# demo_dermis_main_testboard_inamps.net
KiCad netlist of a schematic drawn in Altium Designer
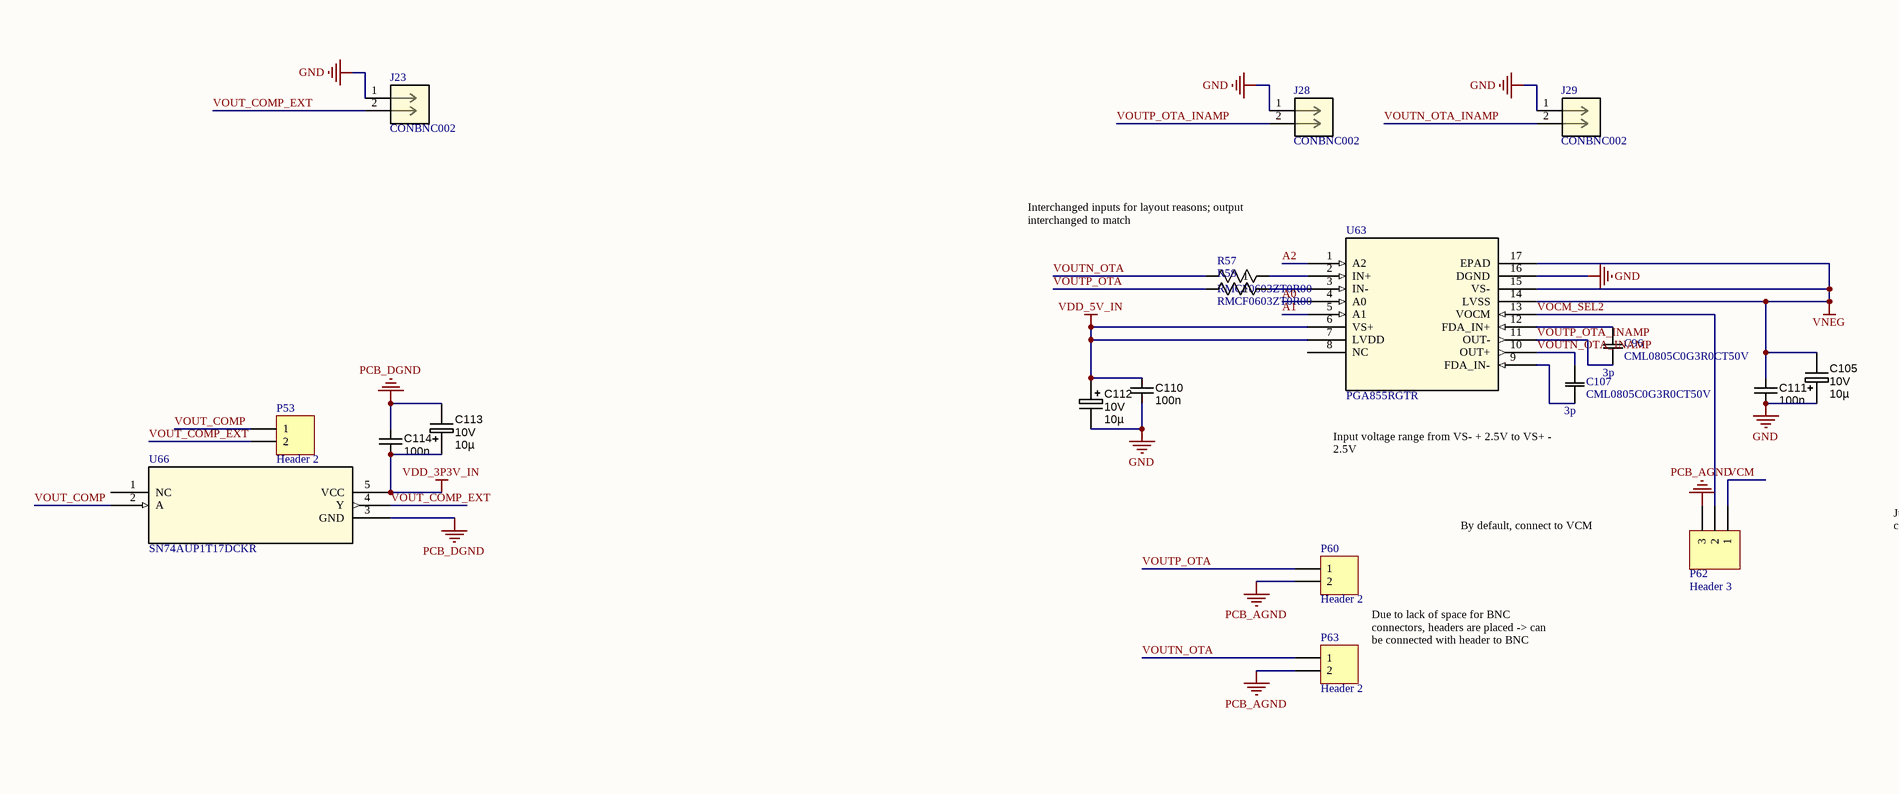
[diagram p0: demo_dermis_main_testboard_inamps.SchDoc, left]
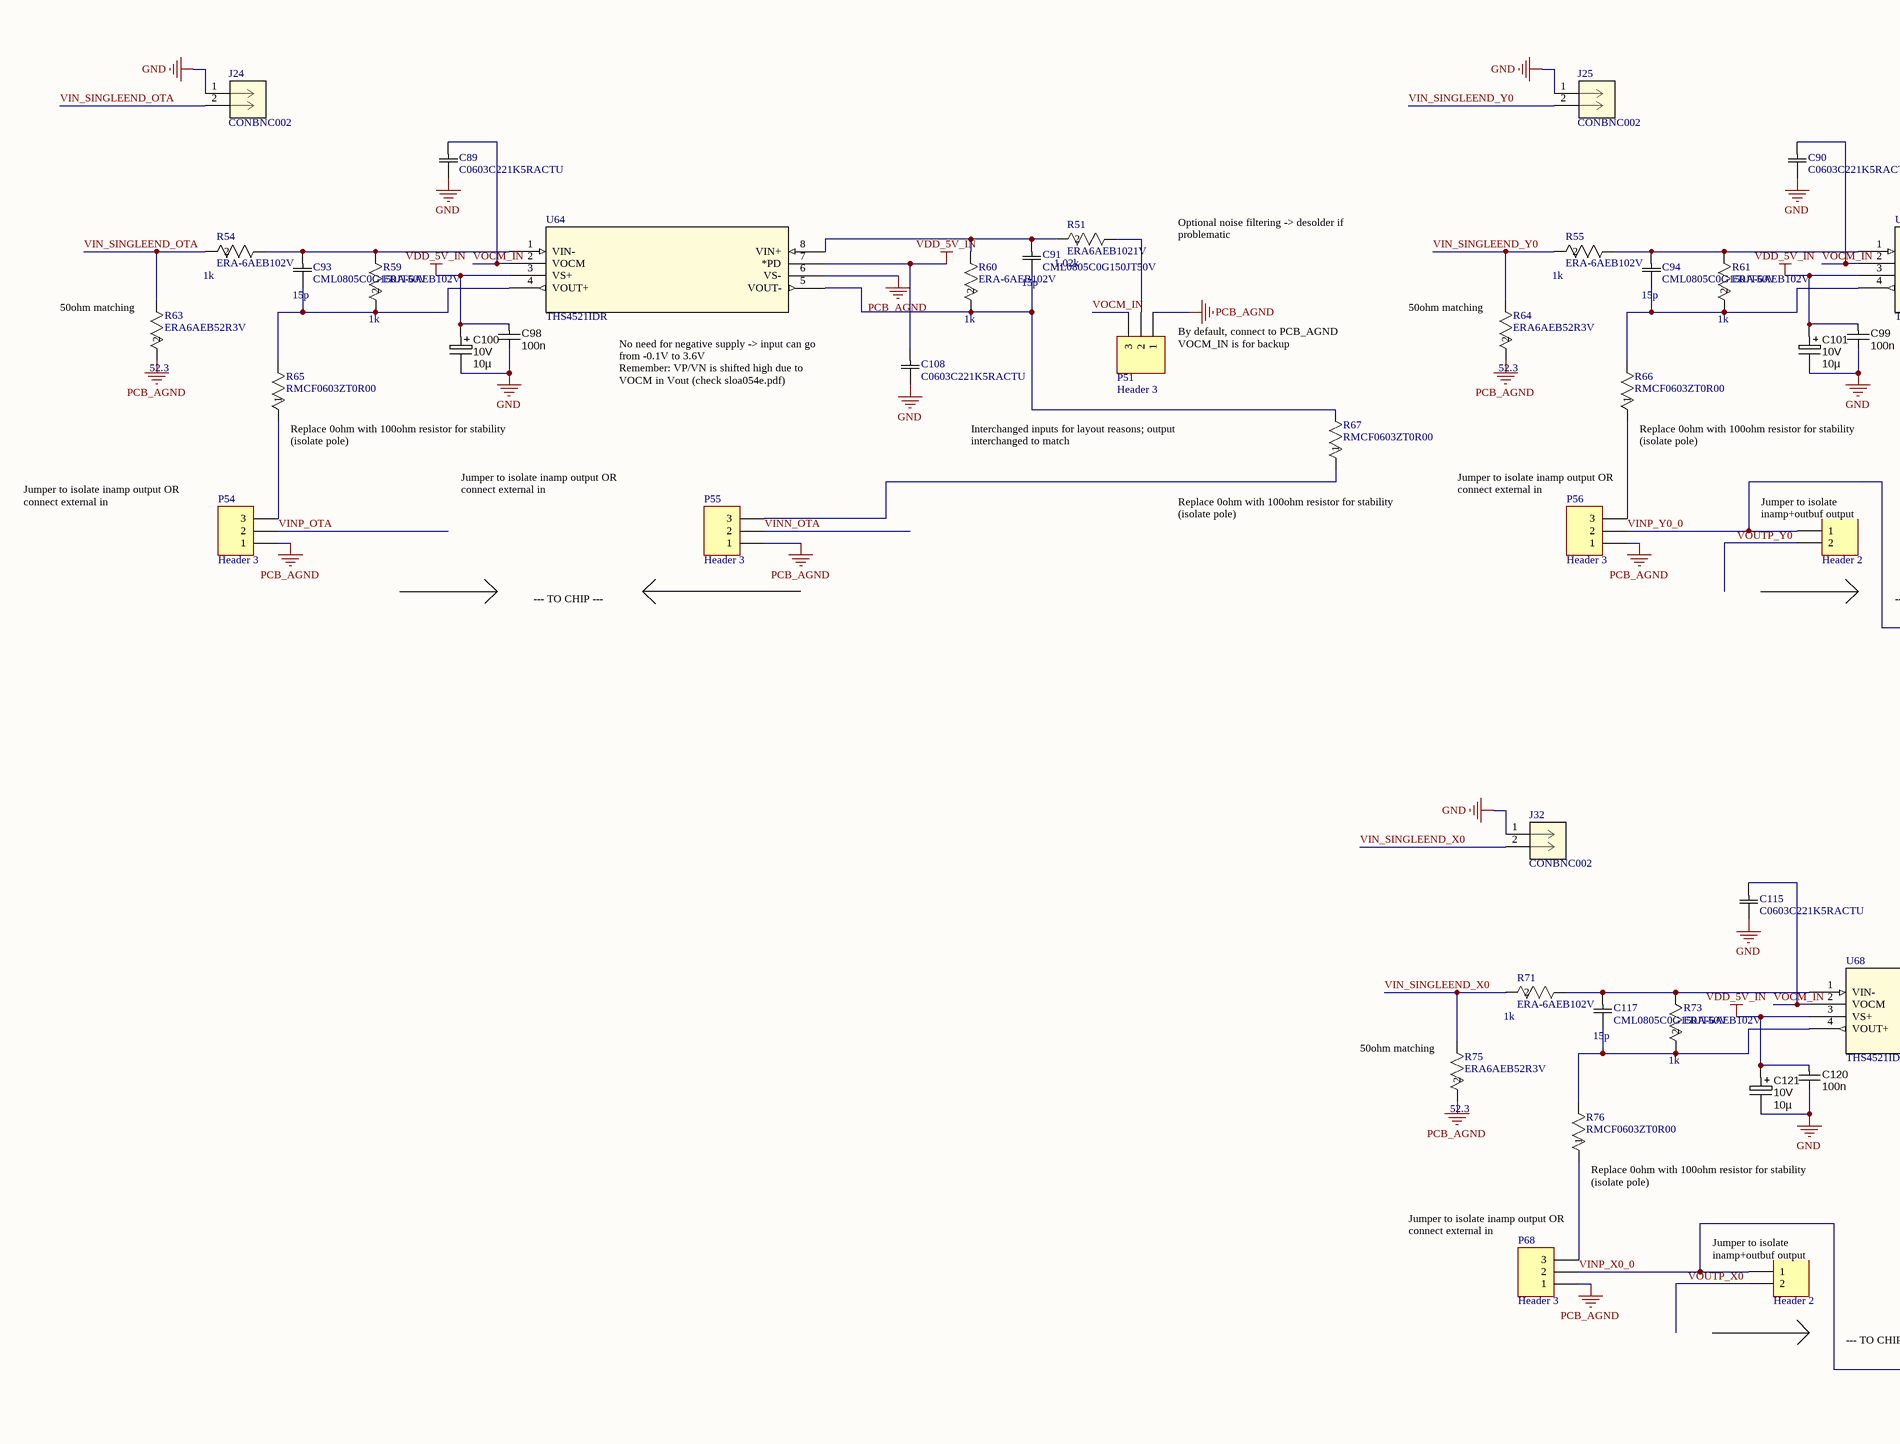
[diagram p1: demo_dermis_main_testboard_inamps.SchDoc, middle]
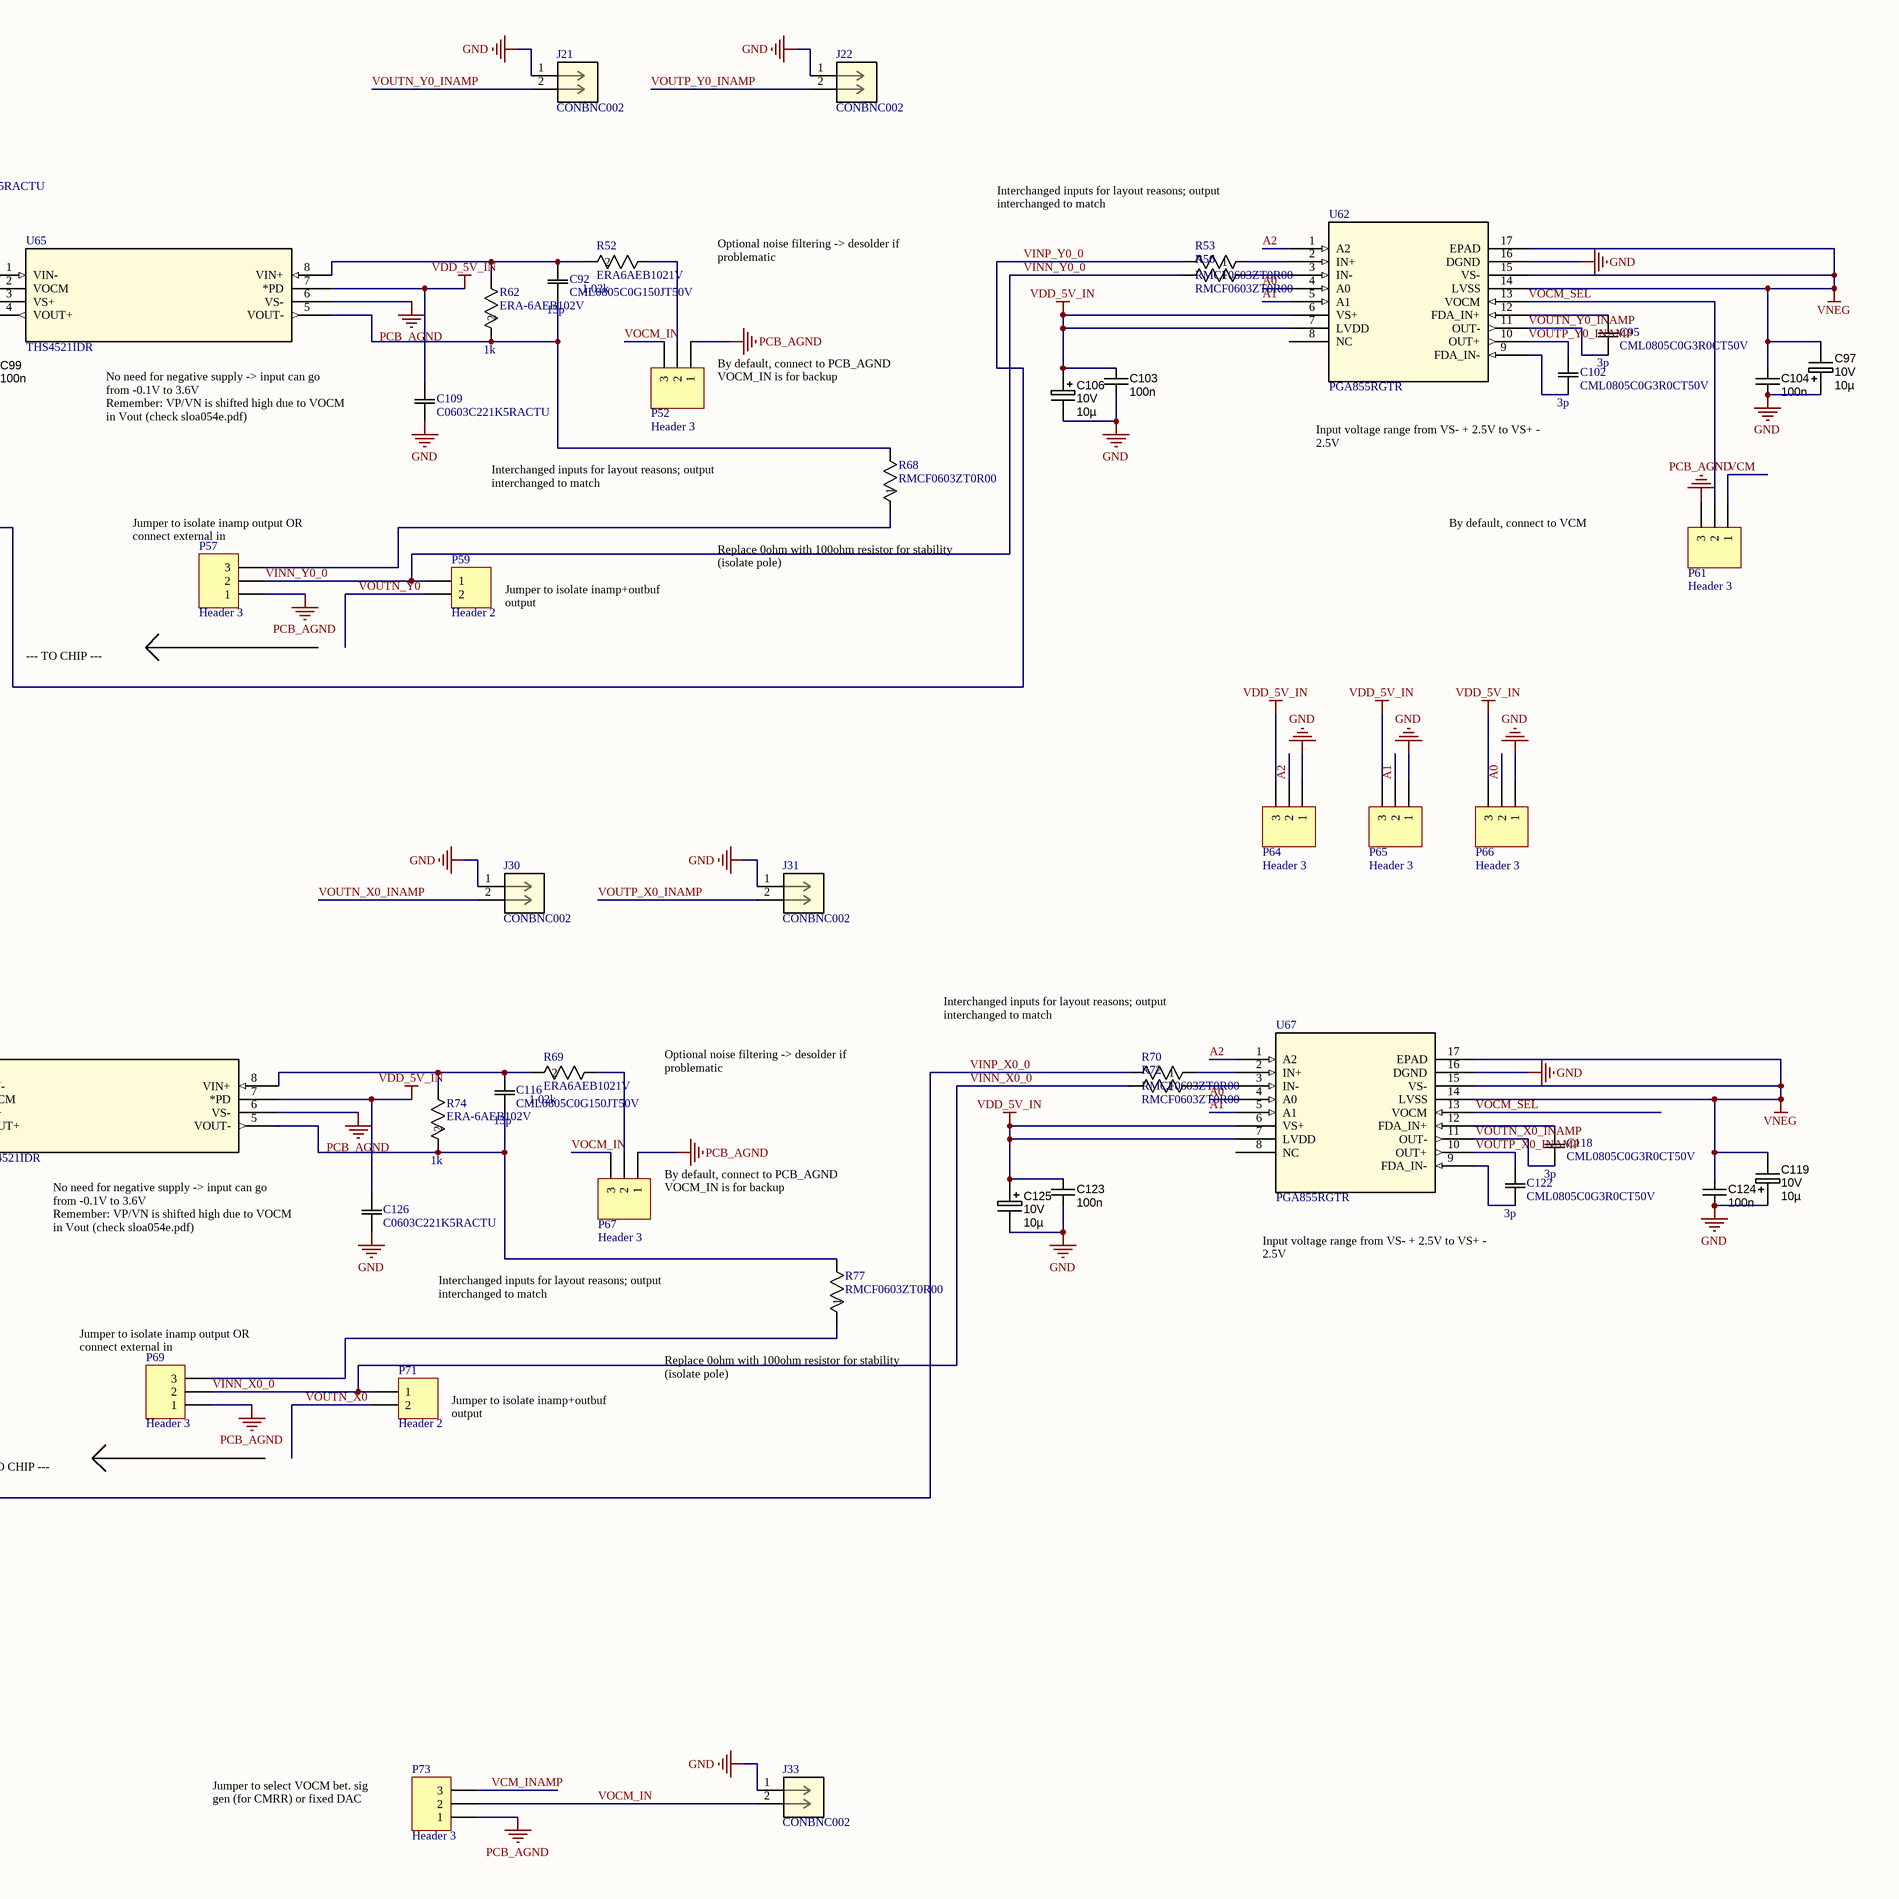
[diagram p2: demo_dermis_main_testboard_inamps.SchDoc, right]

(export (version "E")
  (design (tool "Eeschema 10.0.6"))
  (components
    (comp (ref "C89")
      (value "C0603C221K5RACTU")
      (footprint "CAPC17595_87N_KEM")
      (description "No Description Available")
      (libsource (lib "C0603C221K5RACTU") (part "C0603C221K5RACTU"))
    )
    (comp (ref "C90")
      (value "C0603C221K5RACTU")
      (footprint "CAPC17595_87N_KEM")
      (description "No Description Available")
      (libsource (lib "C0603C221K5RACTU") (part "C0603C221K5RACTU"))
    )
    (comp (ref "C91")
      (value "CML0805C0G150JT50V")
      (footprint "CAP_CML_0805_.3pF-1500pF,4700pF_STP")
      (description "No Description Available")
      (fields (field (name "ALTIUM_VALUE") "15p"))
      (libsource (lib "CML0805C0G150JT50V") (part "CML0805C0G150JT50V"))
    )
    (comp (ref "C92")
      (value "CML0805C0G150JT50V")
      (footprint "CAP_CML_0805_.3pF-1500pF,4700pF_STP")
      (description "No Description Available")
      (fields (field (name "ALTIUM_VALUE") "15p"))
      (libsource (lib "CML0805C0G150JT50V") (part "CML0805C0G150JT50V"))
    )
    (comp (ref "C93")
      (value "CML0805C0G150JT50V")
      (footprint "CAP_CML_0805_.3pF-1500pF,4700pF_STP")
      (description "No Description Available")
      (fields (field (name "ALTIUM_VALUE") "15p"))
      (libsource (lib "CML0805C0G150JT50V") (part "CML0805C0G150JT50V"))
    )
    (comp (ref "C94")
      (value "CML0805C0G150JT50V")
      (footprint "CAP_CML_0805_.3pF-1500pF,4700pF_STP")
      (description "No Description Available")
      (fields (field (name "ALTIUM_VALUE") "15p"))
      (libsource (lib "CML0805C0G150JT50V") (part "CML0805C0G150JT50V"))
    )
    (comp (ref "C95")
      (value "CML0805C0G3R0CT50V")
      (footprint "CAP_CML_0805_.3pF-1500pF,4700pF_STP")
      (description "No Description Available")
      (fields (field (name "ALTIUM_VALUE") "3p"))
      (libsource (lib "CML0805C0G3R0CT50V") (part "CML0805C0G3R0CT50V"))
    )
    (comp (ref "C96")
      (value "CML0805C0G3R0CT50V")
      (footprint "CAP_CML_0805_.3pF-1500pF,4700pF_STP")
      (description "No Description Available")
      (fields (field (name "ALTIUM_VALUE") "3p"))
      (libsource (lib "CML0805C0G3R0CT50V") (part "CML0805C0G3R0CT50V"))
    )
    (comp (ref "C97")
      (value "10µ")
      (footprint "CAPMP2012X150USR")
      (description "Capacitor SMD Tantalum 10uF 20% 10V 0805")
      (fields (field (name "TOLERANCE") "±20%") (field (name "RATINGS") "10V"))
      (libsource (lib "PBL - Capacitors") (part "CAPT_10u_0805_10V"))
    )
    (comp (ref "C98")
      (value "100n")
      (footprint "CAPC1608N")
      (description "Capacitor SMD Cer 100nF 10% 50V X7R 0603")
      (fields (field (name "TOLERANCE") "±10%") (field (name "Comment") "approved sub OK"))
      (libsource (lib "PBL - Capacitors") (part "CAPC_100n_0603"))
    )
    (comp (ref "C99")
      (value "100n")
      (footprint "CAPC1608N")
      (description "Capacitor SMD Cer 100nF 10% 50V X7R 0603")
      (fields (field (name "TOLERANCE") "±10%") (field (name "Comment") "approved sub OK"))
      (libsource (lib "PBL - Capacitors") (part "CAPC_100n_0603"))
    )
    (comp (ref "C100")
      (value "10µ")
      (footprint "CAPMP2012X150USR")
      (description "Capacitor SMD Tantalum 10uF 20% 10V 0805")
      (fields (field (name "TOLERANCE") "±20%") (field (name "RATINGS") "10V"))
      (libsource (lib "PBL - Capacitors") (part "CAPT_10u_0805_10V"))
    )
    (comp (ref "C101")
      (value "10µ")
      (footprint "CAPMP2012X150USR")
      (description "Capacitor SMD Tantalum 10uF 20% 10V 0805")
      (fields (field (name "TOLERANCE") "±20%") (field (name "RATINGS") "10V"))
      (libsource (lib "PBL - Capacitors") (part "CAPT_10u_0805_10V"))
    )
    (comp (ref "C102")
      (value "CML0805C0G3R0CT50V")
      (footprint "CAP_CML_0805_.3pF-1500pF,4700pF_STP")
      (description "No Description Available")
      (fields (field (name "ALTIUM_VALUE") "3p"))
      (libsource (lib "CML0805C0G3R0CT50V") (part "CML0805C0G3R0CT50V"))
    )
    (comp (ref "C103")
      (value "100n")
      (footprint "CAPC1608N")
      (description "Capacitor SMD Cer 100nF 10% 50V X7R 0603")
      (fields (field (name "TOLERANCE") "±10%") (field (name "Comment") "approved sub OK"))
      (libsource (lib "PBL - Capacitors") (part "CAPC_100n_0603"))
    )
    (comp (ref "C104")
      (value "100n")
      (footprint "CAPC1608N")
      (description "Capacitor SMD Cer 100nF 10% 50V X7R 0603")
      (fields (field (name "TOLERANCE") "±10%") (field (name "Comment") "approved sub OK"))
      (libsource (lib "PBL - Capacitors") (part "CAPC_100n_0603"))
    )
    (comp (ref "C105")
      (value "10µ")
      (footprint "CAPMP2012X150USR")
      (description "Capacitor SMD Tantalum 10uF 20% 10V 0805")
      (fields (field (name "TOLERANCE") "±20%") (field (name "RATINGS") "10V"))
      (libsource (lib "PBL - Capacitors") (part "CAPT_10u_0805_10V"))
    )
    (comp (ref "C106")
      (value "10µ")
      (footprint "CAPMP2012X150USR")
      (description "Capacitor SMD Tantalum 10uF 20% 10V 0805")
      (fields (field (name "TOLERANCE") "±20%") (field (name "RATINGS") "10V"))
      (libsource (lib "PBL - Capacitors") (part "CAPT_10u_0805_10V"))
    )
    (comp (ref "C107")
      (value "CML0805C0G3R0CT50V")
      (footprint "CAP_CML_0805_.3pF-1500pF,4700pF_STP")
      (description "No Description Available")
      (fields (field (name "ALTIUM_VALUE") "3p"))
      (libsource (lib "CML0805C0G3R0CT50V") (part "CML0805C0G3R0CT50V"))
    )
    (comp (ref "C108")
      (value "C0603C221K5RACTU")
      (footprint "CAPC17595_87N_KEM")
      (description "No Description Available")
      (libsource (lib "C0603C221K5RACTU") (part "C0603C221K5RACTU"))
    )
    (comp (ref "C109")
      (value "C0603C221K5RACTU")
      (footprint "CAPC17595_87N_KEM")
      (description "No Description Available")
      (libsource (lib "C0603C221K5RACTU") (part "C0603C221K5RACTU"))
    )
    (comp (ref "C110")
      (value "100n")
      (footprint "CAPC1608N")
      (description "Capacitor SMD Cer 100nF 10% 50V X7R 0603")
      (fields (field (name "TOLERANCE") "±10%") (field (name "Comment") "approved sub OK"))
      (libsource (lib "PBL - Capacitors") (part "CAPC_100n_0603"))
    )
    (comp (ref "C111")
      (value "100n")
      (footprint "CAPC1608N")
      (description "Capacitor SMD Cer 100nF 10% 50V X7R 0603")
      (fields (field (name "TOLERANCE") "±10%") (field (name "Comment") "approved sub OK"))
      (libsource (lib "PBL - Capacitors") (part "CAPC_100n_0603"))
    )
    (comp (ref "C112")
      (value "10µ")
      (footprint "CAPMP2012X150USR")
      (description "Capacitor SMD Tantalum 10uF 20% 10V 0805")
      (fields (field (name "TOLERANCE") "±20%") (field (name "RATINGS") "10V"))
      (libsource (lib "PBL - Capacitors") (part "CAPT_10u_0805_10V"))
    )
    (comp (ref "C113")
      (value "10µ")
      (footprint "CAPMP2012X150USR")
      (description "Capacitor SMD Tantalum 10uF 20% 10V 0805")
      (fields (field (name "TOLERANCE") "±20%") (field (name "RATINGS") "10V"))
      (libsource (lib "PBL - Capacitors") (part "CAPT_10u_0805_10V"))
    )
    (comp (ref "C114")
      (value "100n")
      (footprint "CAPC1608N")
      (description "Capacitor SMD Cer 100nF 10% 50V X7R 0603")
      (fields (field (name "TOLERANCE") "±10%") (field (name "Comment") "approved sub OK"))
      (libsource (lib "PBL - Capacitors") (part "CAPC_100n_0603"))
    )
    (comp (ref "C115")
      (value "C0603C221K5RACTU")
      (footprint "CAPC17595_87N_KEM")
      (description "No Description Available")
      (libsource (lib "C0603C221K5RACTU") (part "C0603C221K5RACTU"))
    )
    (comp (ref "C116")
      (value "CML0805C0G150JT50V")
      (footprint "CAP_CML_0805_.3pF-1500pF,4700pF_STP")
      (description "No Description Available")
      (fields (field (name "ALTIUM_VALUE") "15p"))
      (libsource (lib "CML0805C0G150JT50V") (part "CML0805C0G150JT50V"))
    )
    (comp (ref "C117")
      (value "CML0805C0G150JT50V")
      (footprint "CAP_CML_0805_.3pF-1500pF,4700pF_STP")
      (description "No Description Available")
      (fields (field (name "ALTIUM_VALUE") "15p"))
      (libsource (lib "CML0805C0G150JT50V") (part "CML0805C0G150JT50V"))
    )
    (comp (ref "C118")
      (value "CML0805C0G3R0CT50V")
      (footprint "CAP_CML_0805_.3pF-1500pF,4700pF_STP")
      (description "No Description Available")
      (fields (field (name "ALTIUM_VALUE") "3p"))
      (libsource (lib "CML0805C0G3R0CT50V") (part "CML0805C0G3R0CT50V"))
    )
    (comp (ref "C119")
      (value "10µ")
      (footprint "CAPMP2012X150USR")
      (description "Capacitor SMD Tantalum 10uF 20% 10V 0805")
      (fields (field (name "TOLERANCE") "±20%") (field (name "RATINGS") "10V"))
      (libsource (lib "PBL - Capacitors") (part "CAPT_10u_0805_10V"))
    )
    (comp (ref "C120")
      (value "100n")
      (footprint "CAPC1608N")
      (description "Capacitor SMD Cer 100nF 10% 50V X7R 0603")
      (fields (field (name "TOLERANCE") "±10%") (field (name "Comment") "approved sub OK"))
      (libsource (lib "PBL - Capacitors") (part "CAPC_100n_0603"))
    )
    (comp (ref "C121")
      (value "10µ")
      (footprint "CAPMP2012X150USR")
      (description "Capacitor SMD Tantalum 10uF 20% 10V 0805")
      (fields (field (name "TOLERANCE") "±20%") (field (name "RATINGS") "10V"))
      (libsource (lib "PBL - Capacitors") (part "CAPT_10u_0805_10V"))
    )
    (comp (ref "C122")
      (value "CML0805C0G3R0CT50V")
      (footprint "CAP_CML_0805_.3pF-1500pF,4700pF_STP")
      (description "No Description Available")
      (fields (field (name "ALTIUM_VALUE") "3p"))
      (libsource (lib "CML0805C0G3R0CT50V") (part "CML0805C0G3R0CT50V"))
    )
    (comp (ref "C123")
      (value "100n")
      (footprint "CAPC1608N")
      (description "Capacitor SMD Cer 100nF 10% 50V X7R 0603")
      (fields (field (name "TOLERANCE") "±10%") (field (name "Comment") "approved sub OK"))
      (libsource (lib "PBL - Capacitors") (part "CAPC_100n_0603"))
    )
    (comp (ref "C124")
      (value "100n")
      (footprint "CAPC1608N")
      (description "Capacitor SMD Cer 100nF 10% 50V X7R 0603")
      (fields (field (name "TOLERANCE") "±10%") (field (name "Comment") "approved sub OK"))
      (libsource (lib "PBL - Capacitors") (part "CAPC_100n_0603"))
    )
    (comp (ref "C125")
      (value "10µ")
      (footprint "CAPMP2012X150USR")
      (description "Capacitor SMD Tantalum 10uF 20% 10V 0805")
      (fields (field (name "TOLERANCE") "±20%") (field (name "RATINGS") "10V"))
      (libsource (lib "PBL - Capacitors") (part "CAPT_10u_0805_10V"))
    )
    (comp (ref "C126")
      (value "C0603C221K5RACTU")
      (footprint "CAPC17595_87N_KEM")
      (description "No Description Available")
      (libsource (lib "C0603C221K5RACTU") (part "C0603C221K5RACTU"))
    )
    (comp (ref "J21")
      (value "CONBNC002")
      (footprint "CONN_CONBN_LNX")
      (description "No Description Available")
      (libsource (lib "CONBNC002") (part "CONBNC002"))
    )
    (comp (ref "J22")
      (value "CONBNC002")
      (footprint "CONN_CONBN_LNX")
      (description "No Description Available")
      (libsource (lib "CONBNC002") (part "CONBNC002"))
    )
    (comp (ref "J23")
      (value "CONBNC002")
      (footprint "CONN_CONBN_LNX")
      (description "No Description Available")
      (libsource (lib "CONBNC002") (part "CONBNC002"))
    )
    (comp (ref "J24")
      (value "CONBNC002")
      (footprint "CONN_CONBN_LNX")
      (description "No Description Available")
      (libsource (lib "CONBNC002") (part "CONBNC002"))
    )
    (comp (ref "J25")
      (value "CONBNC002")
      (footprint "CONN_CONBN_LNX")
      (description "No Description Available")
      (libsource (lib "CONBNC002") (part "CONBNC002"))
    )
    (comp (ref "J28")
      (value "CONBNC002")
      (footprint "CONN_CONBN_LNX")
      (description "No Description Available")
      (libsource (lib "CONBNC002") (part "CONBNC002"))
    )
    (comp (ref "J29")
      (value "CONBNC002")
      (footprint "CONN_CONBN_LNX")
      (description "No Description Available")
      (libsource (lib "CONBNC002") (part "CONBNC002"))
    )
    (comp (ref "J30")
      (value "CONBNC002")
      (footprint "CONN_CONBN_LNX")
      (description "No Description Available")
      (libsource (lib "CONBNC002") (part "CONBNC002"))
    )
    (comp (ref "J31")
      (value "CONBNC002")
      (footprint "CONN_CONBN_LNX")
      (description "No Description Available")
      (libsource (lib "CONBNC002") (part "CONBNC002"))
    )
    (comp (ref "J32")
      (value "CONBNC002")
      (footprint "CONN_CONBN_LNX")
      (description "No Description Available")
      (libsource (lib "CONBNC002") (part "CONBNC002"))
    )
    (comp (ref "J33")
      (value "CONBNC002")
      (footprint "CONN_CONBN_LNX")
      (description "No Description Available")
      (libsource (lib "CONBNC002") (part "CONBNC002"))
    )
    (comp (ref "P51")
      (value "Header 3")
      (footprint "HDR1X3")
      (description "Header, 3-Pin")
      (fields (field (name "PUBLISHER") "Altium Limited"))
      (libsource (lib "") (part "Header 3_1"))
    )
    (comp (ref "P52")
      (value "Header 3")
      (footprint "HDR1X3")
      (description "Header, 3-Pin")
      (fields (field (name "PUBLISHER") "Altium Limited"))
      (libsource (lib "") (part "Header 3_1"))
    )
    (comp (ref "P53")
      (value "Header 2")
      (footprint "HDR1X2")
      (description "Header, 2-Pin")
      (fields (field (name "PUBLISHER") "Altium Limited"))
      (libsource (lib "Miscellaneous Connectors") (part "Header 2"))
    )
    (comp (ref "P54")
      (value "Header 3")
      (footprint "HDR1X3")
      (description "Header, 3-Pin")
      (fields (field (name "PUBLISHER") "Altium Limited"))
      (libsource (lib "Miscellaneous Connectors") (part "Header 3"))
    )
    (comp (ref "P55")
      (value "Header 3")
      (footprint "HDR1X3")
      (description "Header, 3-Pin")
      (fields (field (name "PUBLISHER") "Altium Limited"))
      (libsource (lib "Miscellaneous Connectors") (part "Header 3"))
    )
    (comp (ref "P56")
      (value "Header 3")
      (footprint "HDR1X3")
      (description "Header, 3-Pin")
      (fields (field (name "PUBLISHER") "Altium Limited"))
      (libsource (lib "Miscellaneous Connectors") (part "Header 3"))
    )
    (comp (ref "P57")
      (value "Header 3")
      (footprint "HDR1X3")
      (description "Header, 3-Pin")
      (fields (field (name "PUBLISHER") "Altium Limited"))
      (libsource (lib "Miscellaneous Connectors") (part "Header 3"))
    )
    (comp (ref "P58")
      (value "Header 2")
      (footprint "HDR1X2")
      (description "Header, 2-Pin")
      (fields (field (name "PUBLISHER") "Altium Limited"))
      (libsource (lib "Miscellaneous Connectors") (part "Header 2"))
    )
    (comp (ref "P59")
      (value "Header 2")
      (footprint "HDR1X2")
      (description "Header, 2-Pin")
      (fields (field (name "PUBLISHER") "Altium Limited"))
      (libsource (lib "Miscellaneous Connectors") (part "Header 2"))
    )
    (comp (ref "P60")
      (value "Header 2")
      (footprint "HDR1X2")
      (description "Header, 2-Pin")
      (fields (field (name "PUBLISHER") "Altium Limited"))
      (libsource (lib "Miscellaneous Connectors") (part "Header 2"))
    )
    (comp (ref "P61")
      (value "Header 3")
      (footprint "HDR1X3")
      (description "Header, 3-Pin")
      (fields (field (name "PUBLISHER") "Altium Limited"))
      (libsource (lib "") (part "Header 3_1"))
    )
    (comp (ref "P62")
      (value "Header 3")
      (footprint "HDR1X3")
      (description "Header, 3-Pin")
      (fields (field (name "PUBLISHER") "Altium Limited"))
      (libsource (lib "") (part "Header 3_1"))
    )
    (comp (ref "P63")
      (value "Header 2")
      (footprint "HDR1X2")
      (description "Header, 2-Pin")
      (fields (field (name "PUBLISHER") "Altium Limited"))
      (libsource (lib "Miscellaneous Connectors") (part "Header 2"))
    )
    (comp (ref "P64")
      (value "Header 3")
      (footprint "HDR1X3")
      (description "Header, 3-Pin")
      (fields (field (name "PUBLISHER") "Altium Limited"))
      (libsource (lib "") (part "Header 3_1"))
    )
    (comp (ref "P65")
      (value "Header 3")
      (footprint "HDR1X3")
      (description "Header, 3-Pin")
      (fields (field (name "PUBLISHER") "Altium Limited"))
      (libsource (lib "") (part "Header 3_1"))
    )
    (comp (ref "P66")
      (value "Header 3")
      (footprint "HDR1X3")
      (description "Header, 3-Pin")
      (fields (field (name "PUBLISHER") "Altium Limited"))
      (libsource (lib "") (part "Header 3_1"))
    )
    (comp (ref "P67")
      (value "Header 3")
      (footprint "HDR1X3")
      (description "Header, 3-Pin")
      (fields (field (name "PUBLISHER") "Altium Limited"))
      (libsource (lib "") (part "Header 3_1"))
    )
    (comp (ref "P68")
      (value "Header 3")
      (footprint "HDR1X3")
      (description "Header, 3-Pin")
      (fields (field (name "PUBLISHER") "Altium Limited"))
      (libsource (lib "Miscellaneous Connectors") (part "Header 3"))
    )
    (comp (ref "P69")
      (value "Header 3")
      (footprint "HDR1X3")
      (description "Header, 3-Pin")
      (fields (field (name "PUBLISHER") "Altium Limited"))
      (libsource (lib "Miscellaneous Connectors") (part "Header 3"))
    )
    (comp (ref "P70")
      (value "Header 2")
      (footprint "HDR1X2")
      (description "Header, 2-Pin")
      (fields (field (name "PUBLISHER") "Altium Limited"))
      (libsource (lib "Miscellaneous Connectors") (part "Header 2"))
    )
    (comp (ref "P71")
      (value "Header 2")
      (footprint "HDR1X2")
      (description "Header, 2-Pin")
      (fields (field (name "PUBLISHER") "Altium Limited"))
      (libsource (lib "Miscellaneous Connectors") (part "Header 2"))
    )
    (comp (ref "P73")
      (value "Header 3")
      (footprint "HDR1X3")
      (description "Header, 3-Pin")
      (fields (field (name "PUBLISHER") "Altium Limited"))
      (libsource (lib "Miscellaneous Connectors") (part "Header 3"))
    )
    (comp (ref "R51")
      (value "ERA6AEB1021V")
      (footprint "RES_ERA6A_0805_PAN")
      (description "No Description Available")
      (fields (field (name "ALTIUM_VALUE") "1.02k"))
      (libsource (lib "ERA6AEB1021V") (part "ERA6AEB1021V"))
    )
    (comp (ref "R52")
      (value "ERA6AEB1021V")
      (footprint "RES_ERA6A_0805_PAN")
      (description "No Description Available")
      (fields (field (name "ALTIUM_VALUE") "1.02k"))
      (libsource (lib "ERA6AEB1021V") (part "ERA6AEB1021V"))
    )
    (comp (ref "R53")
      (value "RMCF0603ZT0R00")
      (footprint "STA_RMCF0603_STP")
      (description "No Description Available")
      (libsource (lib "RMCF0603ZT0R00") (part "RMCF0603ZT0R00"))
    )
    (comp (ref "R54")
      (value "ERA-6AEB102V")
      (footprint "RC0805N_PAN")
      (description "No Description Available")
      (fields (field (name "ALTIUM_VALUE") "1k"))
      (libsource (lib "ERA-6AEB102V") (part "ERA-6AEB102V"))
    )
    (comp (ref "R55")
      (value "ERA-6AEB102V")
      (footprint "RC0805N_PAN")
      (description "No Description Available")
      (fields (field (name "ALTIUM_VALUE") "1k"))
      (libsource (lib "ERA-6AEB102V") (part "ERA-6AEB102V"))
    )
    (comp (ref "R56")
      (value "RMCF0603ZT0R00")
      (footprint "STA_RMCF0603_STP")
      (description "No Description Available")
      (libsource (lib "RMCF0603ZT0R00") (part "RMCF0603ZT0R00"))
    )
    (comp (ref "R57")
      (value "RMCF0603ZT0R00")
      (footprint "STA_RMCF0603_STP")
      (description "No Description Available")
      (libsource (lib "RMCF0603ZT0R00") (part "RMCF0603ZT0R00"))
    )
    (comp (ref "R58")
      (value "RMCF0603ZT0R00")
      (footprint "STA_RMCF0603_STP")
      (description "No Description Available")
      (libsource (lib "RMCF0603ZT0R00") (part "RMCF0603ZT0R00"))
    )
    (comp (ref "R59")
      (value "ERA-6AEB102V")
      (footprint "RC0805N_PAN")
      (description "No Description Available")
      (fields (field (name "ALTIUM_VALUE") "1k"))
      (libsource (lib "ERA-6AEB102V") (part "ERA-6AEB102V"))
    )
    (comp (ref "R60")
      (value "ERA-6AEB102V")
      (footprint "RC0805N_PAN")
      (description "No Description Available")
      (fields (field (name "ALTIUM_VALUE") "1k"))
      (libsource (lib "ERA-6AEB102V") (part "ERA-6AEB102V"))
    )
    (comp (ref "R61")
      (value "ERA-6AEB102V")
      (footprint "RC0805N_PAN")
      (description "No Description Available")
      (fields (field (name "ALTIUM_VALUE") "1k"))
      (libsource (lib "ERA-6AEB102V") (part "ERA-6AEB102V"))
    )
    (comp (ref "R62")
      (value "ERA-6AEB102V")
      (footprint "RC0805N_PAN")
      (description "No Description Available")
      (fields (field (name "ALTIUM_VALUE") "1k"))
      (libsource (lib "ERA-6AEB102V") (part "ERA-6AEB102V"))
    )
    (comp (ref "R63")
      (value "ERA6AEB52R3V")
      (footprint "RES_ERA6A_0805_PAN")
      (description "No Description Available")
      (fields (field (name "ALTIUM_VALUE") "52.3"))
      (libsource (lib "ERA6AEB52R3V") (part "ERA6AEB52R3V"))
    )
    (comp (ref "R64")
      (value "ERA6AEB52R3V")
      (footprint "RES_ERA6A_0805_PAN")
      (description "No Description Available")
      (fields (field (name "ALTIUM_VALUE") "52.3"))
      (libsource (lib "ERA6AEB52R3V") (part "ERA6AEB52R3V"))
    )
    (comp (ref "R65")
      (value "RMCF0603ZT0R00")
      (footprint "STA_RMCF0603_STP")
      (description "No Description Available")
      (libsource (lib "RMCF0603ZT0R00") (part "RMCF0603ZT0R00"))
    )
    (comp (ref "R66")
      (value "RMCF0603ZT0R00")
      (footprint "STA_RMCF0603_STP")
      (description "No Description Available")
      (libsource (lib "RMCF0603ZT0R00") (part "RMCF0603ZT0R00"))
    )
    (comp (ref "R67")
      (value "RMCF0603ZT0R00")
      (footprint "STA_RMCF0603_STP")
      (description "No Description Available")
      (libsource (lib "RMCF0603ZT0R00") (part "RMCF0603ZT0R00"))
    )
    (comp (ref "R68")
      (value "RMCF0603ZT0R00")
      (footprint "STA_RMCF0603_STP")
      (description "No Description Available")
      (libsource (lib "RMCF0603ZT0R00") (part "RMCF0603ZT0R00"))
    )
    (comp (ref "R69")
      (value "ERA6AEB1021V")
      (footprint "RES_ERA6A_0805_PAN")
      (description "No Description Available")
      (fields (field (name "ALTIUM_VALUE") "1.02k"))
      (libsource (lib "ERA6AEB1021V") (part "ERA6AEB1021V"))
    )
    (comp (ref "R70")
      (value "RMCF0603ZT0R00")
      (footprint "STA_RMCF0603_STP")
      (description "No Description Available")
      (libsource (lib "RMCF0603ZT0R00") (part "RMCF0603ZT0R00"))
    )
    (comp (ref "R71")
      (value "ERA-6AEB102V")
      (footprint "RC0805N_PAN")
      (description "No Description Available")
      (fields (field (name "ALTIUM_VALUE") "1k"))
      (libsource (lib "ERA-6AEB102V") (part "ERA-6AEB102V"))
    )
    (comp (ref "R72")
      (value "RMCF0603ZT0R00")
      (footprint "STA_RMCF0603_STP")
      (description "No Description Available")
      (libsource (lib "RMCF0603ZT0R00") (part "RMCF0603ZT0R00"))
    )
    (comp (ref "R73")
      (value "ERA-6AEB102V")
      (footprint "RC0805N_PAN")
      (description "No Description Available")
      (fields (field (name "ALTIUM_VALUE") "1k"))
      (libsource (lib "ERA-6AEB102V") (part "ERA-6AEB102V"))
    )
    (comp (ref "R74")
      (value "ERA-6AEB102V")
      (footprint "RC0805N_PAN")
      (description "No Description Available")
      (fields (field (name "ALTIUM_VALUE") "1k"))
      (libsource (lib "ERA-6AEB102V") (part "ERA-6AEB102V"))
    )
    (comp (ref "R75")
      (value "ERA6AEB52R3V")
      (footprint "RES_ERA6A_0805_PAN")
      (description "No Description Available")
      (fields (field (name "ALTIUM_VALUE") "52.3"))
      (libsource (lib "ERA6AEB52R3V") (part "ERA6AEB52R3V"))
    )
    (comp (ref "R76")
      (value "RMCF0603ZT0R00")
      (footprint "STA_RMCF0603_STP")
      (description "No Description Available")
      (libsource (lib "RMCF0603ZT0R00") (part "RMCF0603ZT0R00"))
    )
    (comp (ref "R77")
      (value "RMCF0603ZT0R00")
      (footprint "STA_RMCF0603_STP")
      (description "No Description Available")
      (libsource (lib "RMCF0603ZT0R00") (part "RMCF0603ZT0R00"))
    )
    (comp (ref "U62")
      (value "PGA855RGTR")
      (footprint "VQFN16_RGT_TEX")
      (description "No Description Available")
      (libsource (lib "PGA855RGTR") (part "PGA855RGTR"))
    )
    (comp (ref "U63")
      (value "PGA855RGTR")
      (footprint "VQFN16_RGT_TEX")
      (description "No Description Available")
      (libsource (lib "PGA855RGTR") (part "PGA855RGTR"))
    )
    (comp (ref "U64")
      (value "THS4521IDR")
      (footprint "D8")
      (description "No Description Available")
      (libsource (lib "THS4521IDR") (part "THS4521IDR"))
    )
    (comp (ref "U65")
      (value "THS4521IDR")
      (footprint "D8")
      (description "No Description Available")
      (libsource (lib "THS4521IDR") (part "THS4521IDR"))
    )
    (comp (ref "U66")
      (value "SN74AUP1T17DCKR")
      (footprint "DCK5")
      (description "No Description Available")
      (libsource (lib "SN74AUP1T17DCKR") (part "SN74AUP1T17DCKR"))
    )
    (comp (ref "U67")
      (value "PGA855RGTR")
      (footprint "VQFN16_RGT_TEX")
      (description "No Description Available")
      (libsource (lib "PGA855RGTR") (part "PGA855RGTR"))
    )
    (comp (ref "U68")
      (value "THS4521IDR")
      (footprint "D8")
      (description "No Description Available")
      (libsource (lib "THS4521IDR") (part "THS4521IDR"))
    )
  )
  (nets
    (net (code "1") (name "/A0") (class "Default")
      (node (ref "P66") (pin "2") (pinfunction "2_2") (pintype "passive"))
      (node (ref "U62") (pin "4") (pinfunction "A0_4") (pintype "input"))
      (node (ref "U63") (pin "4") (pinfunction "A0_4") (pintype "input"))
      (node (ref "U67") (pin "4") (pinfunction "A0_4") (pintype "input"))
    )
    (net (code "2") (name "/A1") (class "Default")
      (node (ref "P65") (pin "2") (pinfunction "2_2") (pintype "passive"))
      (node (ref "U62") (pin "5") (pinfunction "A1_5") (pintype "input"))
      (node (ref "U63") (pin "5") (pinfunction "A1_5") (pintype "input"))
      (node (ref "U67") (pin "5") (pinfunction "A1_5") (pintype "input"))
    )
    (net (code "3") (name "/A2") (class "Default")
      (node (ref "P64") (pin "2") (pinfunction "2_2") (pintype "passive"))
      (node (ref "U62") (pin "1") (pinfunction "A2_1") (pintype "input"))
      (node (ref "U63") (pin "1") (pinfunction "A2_1") (pintype "input"))
      (node (ref "U67") (pin "1") (pinfunction "A2_1") (pintype "input"))
    )
    (net (code "4") (name "/VCM") (class "Default")
      (node (ref "P61") (pin "1") (pinfunction "1_1") (pintype "passive"))
      (node (ref "P62") (pin "1") (pinfunction "1_1") (pintype "passive"))
    )
    (net (code "5") (name "/VCM_INAMP") (class "Default")
      (node (ref "P73") (pin "3") (pinfunction "3_3") (pintype "passive"))
    )
    (net (code "6") (name "/VINN_OTA") (class "Default")
      (node (ref "P55") (pin "2") (pinfunction "2_2") (pintype "passive"))
    )
    (net (code "7") (name "/VINN_X0_0") (class "Default")
      (node (ref "P69") (pin "2") (pinfunction "2_2") (pintype "passive"))
      (node (ref "P71") (pin "1") (pinfunction "1_1") (pintype "passive"))
      (node (ref "R72") (pin "2") (pinfunction "2_2") (pintype "passive"))
    )
    (net (code "8") (name "/VINN_Y0_0") (class "Default")
      (node (ref "P57") (pin "2") (pinfunction "2_2") (pintype "passive"))
      (node (ref "P59") (pin "1") (pinfunction "1_1") (pintype "passive"))
      (node (ref "R56") (pin "2") (pinfunction "2_2") (pintype "passive"))
    )
    (net (code "9") (name "/VINP_OTA") (class "Default")
      (node (ref "P54") (pin "2") (pinfunction "2_2") (pintype "passive"))
    )
    (net (code "10") (name "/VINP_X0_0") (class "Default")
      (node (ref "P68") (pin "2") (pinfunction "2_2") (pintype "passive"))
      (node (ref "P70") (pin "1") (pinfunction "1_1") (pintype "passive"))
      (node (ref "R70") (pin "2") (pinfunction "2_2") (pintype "passive"))
    )
    (net (code "11") (name "/VINP_Y0_0") (class "Default")
      (node (ref "P56") (pin "2") (pinfunction "2_2") (pintype "passive"))
      (node (ref "P58") (pin "1") (pinfunction "1_1") (pintype "passive"))
      (node (ref "R53") (pin "2") (pinfunction "2_2") (pintype "passive"))
    )
    (net (code "12") (name "/VIN_SINGLEEND_OTA") (class "Default")
      (node (ref "J24") (pin "2") (pinfunction "2_2") (pintype "passive"))
      (node (ref "R54") (pin "2") (pinfunction "2_2") (pintype "passive"))
      (node (ref "R63") (pin "1") (pinfunction "1_1") (pintype "passive"))
    )
    (net (code "13") (name "/VIN_SINGLEEND_X0") (class "Default")
      (node (ref "J32") (pin "2") (pinfunction "2_2") (pintype "passive"))
      (node (ref "R71") (pin "2") (pinfunction "2_2") (pintype "passive"))
      (node (ref "R75") (pin "1") (pinfunction "1_1") (pintype "passive"))
    )
    (net (code "14") (name "/VIN_SINGLEEND_Y0") (class "Default")
      (node (ref "J25") (pin "2") (pinfunction "2_2") (pintype "passive"))
      (node (ref "R55") (pin "2") (pinfunction "2_2") (pintype "passive"))
      (node (ref "R64") (pin "1") (pinfunction "1_1") (pintype "passive"))
    )
    (net (code "15") (name "/VOCM_IN") (class "Default")
      (node (ref "C115") (pin "1") (pinfunction "1_1") (pintype "passive"))
      (node (ref "C89") (pin "1") (pinfunction "1_1") (pintype "passive"))
      (node (ref "C90") (pin "1") (pinfunction "1_1") (pintype "passive"))
      (node (ref "J33") (pin "2") (pinfunction "2_2") (pintype "passive"))
      (node (ref "P51") (pin "3") (pinfunction "3_3") (pintype "passive"))
      (node (ref "P52") (pin "3") (pinfunction "3_3") (pintype "passive"))
      (node (ref "P67") (pin "3") (pinfunction "3_3") (pintype "passive"))
      (node (ref "P73") (pin "2") (pinfunction "2_2") (pintype "passive"))
      (node (ref "U64") (pin "2") (pinfunction "VOCM_2") (pintype "passive"))
      (node (ref "U65") (pin "2") (pinfunction "VOCM_2") (pintype "passive"))
      (node (ref "U68") (pin "2") (pinfunction "VOCM_2") (pintype "passive"))
    )
    (net (code "16") (name "/VOCM_SEL") (class "Default")
      (node (ref "P61") (pin "2") (pinfunction "2_2") (pintype "passive"))
      (node (ref "U62") (pin "13") (pinfunction "VOCM_13") (pintype "input"))
      (node (ref "U67") (pin "13") (pinfunction "VOCM_13") (pintype "input"))
    )
    (net (code "17") (name "/VOCM_SEL2") (class "Default")
      (node (ref "P62") (pin "2") (pinfunction "2_2") (pintype "passive"))
      (node (ref "U63") (pin "13") (pinfunction "VOCM_13") (pintype "input"))
    )
    (net (code "18") (name "/VOUTN_OTA") (class "Default")
      (node (ref "P63") (pin "1") (pinfunction "1_1") (pintype "passive"))
      (node (ref "R57") (pin "2") (pinfunction "2_2") (pintype "passive"))
    )
    (net (code "19") (name "/VOUTN_OTA_INAMP") (class "Default")
      (node (ref "C107") (pin "2") (pinfunction "2_2") (pintype "passive"))
      (node (ref "J29") (pin "2") (pinfunction "2_2") (pintype "passive"))
      (node (ref "U63") (pin "10") (pinfunction "OUT+_10") (pintype "output"))
    )
    (net (code "20") (name "/VOUTN_X0") (class "Default")
      (node (ref "P71") (pin "2") (pinfunction "2_2") (pintype "passive"))
    )
    (net (code "21") (name "/VOUTN_X0_INAMP") (class "Default")
      (node (ref "C118") (pin "1") (pinfunction "1_1") (pintype "passive"))
      (node (ref "J30") (pin "2") (pinfunction "2_2") (pintype "passive"))
      (node (ref "U67") (pin "11") (pinfunction "OUT-_11") (pintype "output"))
    )
    (net (code "22") (name "/VOUTN_Y0") (class "Default")
      (node (ref "P59") (pin "2") (pinfunction "2_2") (pintype "passive"))
    )
    (net (code "23") (name "/VOUTN_Y0_INAMP") (class "Default")
      (node (ref "C95") (pin "1") (pinfunction "1_1") (pintype "passive"))
      (node (ref "J21") (pin "2") (pinfunction "2_2") (pintype "passive"))
      (node (ref "U62") (pin "11") (pinfunction "OUT-_11") (pintype "output"))
    )
    (net (code "24") (name "/VOUTP_OTA") (class "Default")
      (node (ref "P60") (pin "1") (pinfunction "1_1") (pintype "passive"))
      (node (ref "R58") (pin "2") (pinfunction "2_2") (pintype "passive"))
    )
    (net (code "25") (name "/VOUTP_OTA_INAMP") (class "Default")
      (node (ref "C96") (pin "1") (pinfunction "1_1") (pintype "passive"))
      (node (ref "J28") (pin "2") (pinfunction "2_2") (pintype "passive"))
      (node (ref "U63") (pin "11") (pinfunction "OUT-_11") (pintype "output"))
    )
    (net (code "26") (name "/VOUTP_X0") (class "Default")
      (node (ref "P70") (pin "2") (pinfunction "2_2") (pintype "passive"))
    )
    (net (code "27") (name "/VOUTP_X0_INAMP") (class "Default")
      (node (ref "C122") (pin "2") (pinfunction "2_2") (pintype "passive"))
      (node (ref "J31") (pin "2") (pinfunction "2_2") (pintype "passive"))
      (node (ref "U67") (pin "10") (pinfunction "OUT+_10") (pintype "output"))
    )
    (net (code "28") (name "/VOUTP_Y0") (class "Default")
      (node (ref "P58") (pin "2") (pinfunction "2_2") (pintype "passive"))
    )
    (net (code "29") (name "/VOUTP_Y0_INAMP") (class "Default")
      (node (ref "C102") (pin "2") (pinfunction "2_2") (pintype "passive"))
      (node (ref "J22") (pin "2") (pinfunction "2_2") (pintype "passive"))
      (node (ref "U62") (pin "10") (pinfunction "OUT+_10") (pintype "output"))
    )
    (net (code "30") (name "/VOUT_COMP") (class "Default")
      (node (ref "P53") (pin "1") (pinfunction "1_1") (pintype "passive"))
      (node (ref "U66") (pin "2") (pinfunction "A_2") (pintype "input"))
    )
    (net (code "31") (name "/VOUT_COMP_EXT") (class "Default")
      (node (ref "J23") (pin "2") (pinfunction "2_2") (pintype "passive"))
      (node (ref "P53") (pin "2") (pinfunction "2_2") (pintype "passive"))
      (node (ref "U66") (pin "4") (pinfunction "Y_4") (pintype "output"))
    )
    (net (code "32") (name "GND") (class "Default")
      (node (ref "C100") (pin "2") (pintype "passive"))
      (node (ref "C101") (pin "2") (pintype "passive"))
      (node (ref "C103") (pin "2") (pintype "passive"))
      (node (ref "C104") (pin "1") (pintype "passive"))
      (node (ref "C105") (pin "1") (pintype "passive"))
      (node (ref "C106") (pin "2") (pintype "passive"))
      (node (ref "C108") (pin "2") (pinfunction "2_2") (pintype "passive"))
      (node (ref "C109") (pin "2") (pinfunction "2_2") (pintype "passive"))
      (node (ref "C110") (pin "2") (pintype "passive"))
      (node (ref "C111") (pin "1") (pintype "passive"))
      (node (ref "C112") (pin "2") (pintype "passive"))
      (node (ref "C115") (pin "2") (pinfunction "2_2") (pintype "passive"))
      (node (ref "C119") (pin "1") (pintype "passive"))
      (node (ref "C120") (pin "2") (pintype "passive"))
      (node (ref "C121") (pin "2") (pintype "passive"))
      (node (ref "C123") (pin "2") (pintype "passive"))
      (node (ref "C124") (pin "1") (pintype "passive"))
      (node (ref "C125") (pin "2") (pintype "passive"))
      (node (ref "C126") (pin "2") (pinfunction "2_2") (pintype "passive"))
      (node (ref "C89") (pin "2") (pinfunction "2_2") (pintype "passive"))
      (node (ref "C90") (pin "2") (pinfunction "2_2") (pintype "passive"))
      (node (ref "C97") (pin "1") (pintype "passive"))
      (node (ref "C98") (pin "2") (pintype "passive"))
      (node (ref "C99") (pin "2") (pintype "passive"))
      (node (ref "J21") (pin "1") (pinfunction "1_1") (pintype "passive"))
      (node (ref "J22") (pin "1") (pinfunction "1_1") (pintype "passive"))
      (node (ref "J23") (pin "1") (pinfunction "1_1") (pintype "passive"))
      (node (ref "J24") (pin "1") (pinfunction "1_1") (pintype "passive"))
      (node (ref "J25") (pin "1") (pinfunction "1_1") (pintype "passive"))
      (node (ref "J28") (pin "1") (pinfunction "1_1") (pintype "passive"))
      (node (ref "J29") (pin "1") (pinfunction "1_1") (pintype "passive"))
      (node (ref "J30") (pin "1") (pinfunction "1_1") (pintype "passive"))
      (node (ref "J31") (pin "1") (pinfunction "1_1") (pintype "passive"))
      (node (ref "J32") (pin "1") (pinfunction "1_1") (pintype "passive"))
      (node (ref "J33") (pin "1") (pinfunction "1_1") (pintype "passive"))
      (node (ref "P64") (pin "1") (pinfunction "1_1") (pintype "passive"))
      (node (ref "P65") (pin "1") (pinfunction "1_1") (pintype "passive"))
      (node (ref "P66") (pin "1") (pinfunction "1_1") (pintype "passive"))
      (node (ref "U62") (pin "16") (pinfunction "DGND_16") (pintype "power_in"))
      (node (ref "U63") (pin "16") (pinfunction "DGND_16") (pintype "power_in"))
      (node (ref "U67") (pin "16") (pinfunction "DGND_16") (pintype "power_in"))
    )
    (net (code "33") (name "Net-(P51-Pad2)") (class "Default")
      (node (ref "P51") (pin "2") (pinfunction "2_2") (pintype "passive"))
      (node (ref "R51") (pin "1") (pinfunction "1_1") (pintype "passive"))
    )
    (net (code "34") (name "Net-(P52-Pad2)") (class "Default")
      (node (ref "P52") (pin "2") (pinfunction "2_2") (pintype "passive"))
      (node (ref "R52") (pin "1") (pinfunction "1_1") (pintype "passive"))
    )
    (net (code "35") (name "Net-(P54-Pad3)") (class "Default")
      (node (ref "P54") (pin "3") (pinfunction "3_3") (pintype "passive"))
      (node (ref "R65") (pin "1") (pinfunction "1_1") (pintype "passive"))
    )
    (net (code "36") (name "Net-(P55-Pad3)") (class "Default")
      (node (ref "P55") (pin "3") (pinfunction "3_3") (pintype "passive"))
      (node (ref "R67") (pin "1") (pinfunction "1_1") (pintype "passive"))
    )
    (net (code "37") (name "Net-(P56-Pad3)") (class "Default")
      (node (ref "P56") (pin "3") (pinfunction "3_3") (pintype "passive"))
      (node (ref "R66") (pin "1") (pinfunction "1_1") (pintype "passive"))
    )
    (net (code "38") (name "Net-(P57-Pad3)") (class "Default")
      (node (ref "P57") (pin "3") (pinfunction "3_3") (pintype "passive"))
      (node (ref "R68") (pin "1") (pinfunction "1_1") (pintype "passive"))
    )
    (net (code "39") (name "Net-(P67-Pad2)") (class "Default")
      (node (ref "P67") (pin "2") (pinfunction "2_2") (pintype "passive"))
      (node (ref "R69") (pin "1") (pinfunction "1_1") (pintype "passive"))
    )
    (net (code "40") (name "Net-(P68-Pad3)") (class "Default")
      (node (ref "P68") (pin "3") (pinfunction "3_3") (pintype "passive"))
      (node (ref "R76") (pin "1") (pinfunction "1_1") (pintype "passive"))
    )
    (net (code "41") (name "Net-(P69-Pad3)") (class "Default")
      (node (ref "P69") (pin "3") (pinfunction "3_3") (pintype "passive"))
      (node (ref "R77") (pin "1") (pinfunction "1_1") (pintype "passive"))
    )
    (net (code "42") (name "Net-(U62-FDA_IN+)") (class "Default")
      (node (ref "C95") (pin "2") (pinfunction "2_2") (pintype "passive"))
      (node (ref "U62") (pin "12") (pinfunction "FDA_IN+_12") (pintype "input"))
    )
    (net (code "43") (name "Net-(U62-FDA_IN-)") (class "Default")
      (node (ref "C102") (pin "1") (pinfunction "1_1") (pintype "passive"))
      (node (ref "U62") (pin "9") (pinfunction "FDA_IN-_9") (pintype "input"))
    )
    (net (code "44") (name "Net-(U62-IN+)") (class "Default")
      (node (ref "R53") (pin "1") (pinfunction "1_1") (pintype "passive"))
      (node (ref "U62") (pin "2") (pinfunction "IN+_2") (pintype "input"))
    )
    (net (code "45") (name "Net-(U62-IN-)") (class "Default")
      (node (ref "R56") (pin "1") (pinfunction "1_1") (pintype "passive"))
      (node (ref "U62") (pin "3") (pinfunction "IN-_3") (pintype "input"))
    )
    (net (code "46") (name "Net-(U63-FDA_IN+)") (class "Default")
      (node (ref "C96") (pin "2") (pinfunction "2_2") (pintype "passive"))
      (node (ref "U63") (pin "12") (pinfunction "FDA_IN+_12") (pintype "input"))
    )
    (net (code "47") (name "Net-(U63-FDA_IN-)") (class "Default")
      (node (ref "C107") (pin "1") (pinfunction "1_1") (pintype "passive"))
      (node (ref "U63") (pin "9") (pinfunction "FDA_IN-_9") (pintype "input"))
    )
    (net (code "48") (name "Net-(U63-IN+)") (class "Default")
      (node (ref "R57") (pin "1") (pinfunction "1_1") (pintype "passive"))
      (node (ref "U63") (pin "2") (pinfunction "IN+_2") (pintype "input"))
    )
    (net (code "49") (name "Net-(U63-IN-)") (class "Default")
      (node (ref "R58") (pin "1") (pinfunction "1_1") (pintype "passive"))
      (node (ref "U63") (pin "3") (pinfunction "IN-_3") (pintype "input"))
    )
    (net (code "50") (name "Net-(U64-VIN+)") (class "Default")
      (node (ref "C91") (pin "1") (pinfunction "1_1") (pintype "passive"))
      (node (ref "R51") (pin "2") (pinfunction "2_2") (pintype "passive"))
      (node (ref "R60") (pin "1") (pinfunction "1_1") (pintype "passive"))
      (node (ref "U64") (pin "8") (pinfunction "VIN+_8") (pintype "input"))
    )
    (net (code "51") (name "Net-(U64-VIN-)") (class "Default")
      (node (ref "C93") (pin "1") (pinfunction "1_1") (pintype "passive"))
      (node (ref "R54") (pin "1") (pinfunction "1_1") (pintype "passive"))
      (node (ref "R59") (pin "1") (pinfunction "1_1") (pintype "passive"))
      (node (ref "U64") (pin "1") (pinfunction "VIN-_1") (pintype "input"))
    )
    (net (code "52") (name "Net-(U64-VOUT+)") (class "Default")
      (node (ref "C93") (pin "2") (pinfunction "2_2") (pintype "passive"))
      (node (ref "R59") (pin "2") (pinfunction "2_2") (pintype "passive"))
      (node (ref "R65") (pin "2") (pinfunction "2_2") (pintype "passive"))
      (node (ref "U64") (pin "4") (pinfunction "VOUT+_4") (pintype "output"))
    )
    (net (code "53") (name "Net-(U64-VOUT-)") (class "Default")
      (node (ref "C91") (pin "2") (pinfunction "2_2") (pintype "passive"))
      (node (ref "R60") (pin "2") (pinfunction "2_2") (pintype "passive"))
      (node (ref "R67") (pin "2") (pinfunction "2_2") (pintype "passive"))
      (node (ref "U64") (pin "5") (pinfunction "VOUT-_5") (pintype "output"))
    )
    (net (code "54") (name "Net-(U65-VIN+)") (class "Default")
      (node (ref "C92") (pin "1") (pinfunction "1_1") (pintype "passive"))
      (node (ref "R52") (pin "2") (pinfunction "2_2") (pintype "passive"))
      (node (ref "R62") (pin "1") (pinfunction "1_1") (pintype "passive"))
      (node (ref "U65") (pin "8") (pinfunction "VIN+_8") (pintype "input"))
    )
    (net (code "55") (name "Net-(U65-VIN-)") (class "Default")
      (node (ref "C94") (pin "1") (pinfunction "1_1") (pintype "passive"))
      (node (ref "R55") (pin "1") (pinfunction "1_1") (pintype "passive"))
      (node (ref "R61") (pin "1") (pinfunction "1_1") (pintype "passive"))
      (node (ref "U65") (pin "1") (pinfunction "VIN-_1") (pintype "input"))
    )
    (net (code "56") (name "Net-(U65-VOUT+)") (class "Default")
      (node (ref "C94") (pin "2") (pinfunction "2_2") (pintype "passive"))
      (node (ref "R61") (pin "2") (pinfunction "2_2") (pintype "passive"))
      (node (ref "R66") (pin "2") (pinfunction "2_2") (pintype "passive"))
      (node (ref "U65") (pin "4") (pinfunction "VOUT+_4") (pintype "output"))
    )
    (net (code "57") (name "Net-(U65-VOUT-)") (class "Default")
      (node (ref "C92") (pin "2") (pinfunction "2_2") (pintype "passive"))
      (node (ref "R62") (pin "2") (pinfunction "2_2") (pintype "passive"))
      (node (ref "R68") (pin "2") (pinfunction "2_2") (pintype "passive"))
      (node (ref "U65") (pin "5") (pinfunction "VOUT-_5") (pintype "output"))
    )
    (net (code "58") (name "Net-(U67-FDA_IN+)") (class "Default")
      (node (ref "C118") (pin "2") (pinfunction "2_2") (pintype "passive"))
      (node (ref "U67") (pin "12") (pinfunction "FDA_IN+_12") (pintype "input"))
    )
    (net (code "59") (name "Net-(U67-FDA_IN-)") (class "Default")
      (node (ref "C122") (pin "1") (pinfunction "1_1") (pintype "passive"))
      (node (ref "U67") (pin "9") (pinfunction "FDA_IN-_9") (pintype "input"))
    )
    (net (code "60") (name "Net-(U67-IN+)") (class "Default")
      (node (ref "R70") (pin "1") (pinfunction "1_1") (pintype "passive"))
      (node (ref "U67") (pin "2") (pinfunction "IN+_2") (pintype "input"))
    )
    (net (code "61") (name "Net-(U67-IN-)") (class "Default")
      (node (ref "R72") (pin "1") (pinfunction "1_1") (pintype "passive"))
      (node (ref "U67") (pin "3") (pinfunction "IN-_3") (pintype "input"))
    )
    (net (code "62") (name "Net-(U68-VIN+)") (class "Default")
      (node (ref "C116") (pin "1") (pinfunction "1_1") (pintype "passive"))
      (node (ref "R69") (pin "2") (pinfunction "2_2") (pintype "passive"))
      (node (ref "R74") (pin "1") (pinfunction "1_1") (pintype "passive"))
      (node (ref "U68") (pin "8") (pinfunction "VIN+_8") (pintype "input"))
    )
    (net (code "63") (name "Net-(U68-VIN-)") (class "Default")
      (node (ref "C117") (pin "1") (pinfunction "1_1") (pintype "passive"))
      (node (ref "R71") (pin "1") (pinfunction "1_1") (pintype "passive"))
      (node (ref "R73") (pin "1") (pinfunction "1_1") (pintype "passive"))
      (node (ref "U68") (pin "1") (pinfunction "VIN-_1") (pintype "input"))
    )
    (net (code "64") (name "Net-(U68-VOUT+)") (class "Default")
      (node (ref "C117") (pin "2") (pinfunction "2_2") (pintype "passive"))
      (node (ref "R73") (pin "2") (pinfunction "2_2") (pintype "passive"))
      (node (ref "R76") (pin "2") (pinfunction "2_2") (pintype "passive"))
      (node (ref "U68") (pin "4") (pinfunction "VOUT+_4") (pintype "output"))
    )
    (net (code "65") (name "Net-(U68-VOUT-)") (class "Default")
      (node (ref "C116") (pin "2") (pinfunction "2_2") (pintype "passive"))
      (node (ref "R74") (pin "2") (pinfunction "2_2") (pintype "passive"))
      (node (ref "R77") (pin "2") (pinfunction "2_2") (pintype "passive"))
      (node (ref "U68") (pin "5") (pinfunction "VOUT-_5") (pintype "output"))
    )
    (net (code "66") (name "PCB_AGND") (class "Default")
      (node (ref "P51") (pin "1") (pinfunction "1_1") (pintype "passive"))
      (node (ref "P52") (pin "1") (pinfunction "1_1") (pintype "passive"))
      (node (ref "P54") (pin "1") (pinfunction "1_1") (pintype "passive"))
      (node (ref "P55") (pin "1") (pinfunction "1_1") (pintype "passive"))
      (node (ref "P56") (pin "1") (pinfunction "1_1") (pintype "passive"))
      (node (ref "P57") (pin "1") (pinfunction "1_1") (pintype "passive"))
      (node (ref "P60") (pin "2") (pinfunction "2_2") (pintype "passive"))
      (node (ref "P61") (pin "3") (pinfunction "3_3") (pintype "passive"))
      (node (ref "P62") (pin "3") (pinfunction "3_3") (pintype "passive"))
      (node (ref "P63") (pin "2") (pinfunction "2_2") (pintype "passive"))
      (node (ref "P67") (pin "1") (pinfunction "1_1") (pintype "passive"))
      (node (ref "P68") (pin "1") (pinfunction "1_1") (pintype "passive"))
      (node (ref "P69") (pin "1") (pinfunction "1_1") (pintype "passive"))
      (node (ref "P73") (pin "1") (pinfunction "1_1") (pintype "passive"))
      (node (ref "R63") (pin "2") (pinfunction "2_2") (pintype "passive"))
      (node (ref "R64") (pin "2") (pinfunction "2_2") (pintype "passive"))
      (node (ref "R75") (pin "2") (pinfunction "2_2") (pintype "passive"))
      (node (ref "U64") (pin "6") (pinfunction "VS-_6") (pintype "power_in"))
      (node (ref "U65") (pin "6") (pinfunction "VS-_6") (pintype "power_in"))
      (node (ref "U68") (pin "6") (pinfunction "VS-_6") (pintype "power_in"))
    )
    (net (code "67") (name "PCB_DGND") (class "Default")
      (node (ref "C113") (pin "2") (pintype "passive"))
      (node (ref "C114") (pin "2") (pintype "passive"))
      (node (ref "U66") (pin "3") (pinfunction "GND_3") (pintype "power_in"))
    )
    (net (code "68") (name "VDD_3P3V_IN") (class "Default")
      (node (ref "C113") (pin "1") (pintype "passive"))
      (node (ref "C114") (pin "1") (pintype "passive"))
      (node (ref "U66") (pin "5") (pinfunction "VCC_5") (pintype "power_in"))
    )
    (net (code "69") (name "VDD_5V_IN") (class "Default")
      (node (ref "C100") (pin "1") (pintype "passive"))
      (node (ref "C101") (pin "1") (pintype "passive"))
      (node (ref "C103") (pin "1") (pintype "passive"))
      (node (ref "C106") (pin "1") (pintype "passive"))
      (node (ref "C108") (pin "1") (pinfunction "1_1") (pintype "passive"))
      (node (ref "C109") (pin "1") (pinfunction "1_1") (pintype "passive"))
      (node (ref "C110") (pin "1") (pintype "passive"))
      (node (ref "C112") (pin "1") (pintype "passive"))
      (node (ref "C120") (pin "1") (pintype "passive"))
      (node (ref "C121") (pin "1") (pintype "passive"))
      (node (ref "C123") (pin "1") (pintype "passive"))
      (node (ref "C125") (pin "1") (pintype "passive"))
      (node (ref "C126") (pin "1") (pinfunction "1_1") (pintype "passive"))
      (node (ref "C98") (pin "1") (pintype "passive"))
      (node (ref "C99") (pin "1") (pintype "passive"))
      (node (ref "P64") (pin "3") (pinfunction "3_3") (pintype "passive"))
      (node (ref "P65") (pin "3") (pinfunction "3_3") (pintype "passive"))
      (node (ref "P66") (pin "3") (pinfunction "3_3") (pintype "passive"))
      (node (ref "U62") (pin "6") (pinfunction "VS+_6") (pintype "power_in"))
      (node (ref "U62") (pin "7") (pinfunction "LVDD_7") (pintype "power_in"))
      (node (ref "U63") (pin "6") (pinfunction "VS+_6") (pintype "power_in"))
      (node (ref "U63") (pin "7") (pinfunction "LVDD_7") (pintype "power_in"))
      (node (ref "U64") (pin "3") (pinfunction "VS+_3") (pintype "power_in"))
      (node (ref "U64") (pin "7") (pinfunction "*PD_7") (pintype "passive"))
      (node (ref "U65") (pin "3") (pinfunction "VS+_3") (pintype "power_in"))
      (node (ref "U65") (pin "7") (pinfunction "*PD_7") (pintype "passive"))
      (node (ref "U67") (pin "6") (pinfunction "VS+_6") (pintype "power_in"))
      (node (ref "U67") (pin "7") (pinfunction "LVDD_7") (pintype "power_in"))
      (node (ref "U68") (pin "3") (pinfunction "VS+_3") (pintype "power_in"))
      (node (ref "U68") (pin "7") (pinfunction "*PD_7") (pintype "passive"))
    )
    (net (code "70") (name "VNEG") (class "Default")
      (node (ref "C104") (pin "2") (pintype "passive"))
      (node (ref "C105") (pin "2") (pintype "passive"))
      (node (ref "C111") (pin "2") (pintype "passive"))
      (node (ref "C119") (pin "2") (pintype "passive"))
      (node (ref "C124") (pin "2") (pintype "passive"))
      (node (ref "C97") (pin "2") (pintype "passive"))
      (node (ref "U62") (pin "14") (pinfunction "LVSS_14") (pintype "power_in"))
      (node (ref "U62") (pin "15") (pinfunction "VS-_15") (pintype "power_in"))
      (node (ref "U62") (pin "17") (pinfunction "EPAD_17") (pintype "passive"))
      (node (ref "U63") (pin "14") (pinfunction "LVSS_14") (pintype "power_in"))
      (node (ref "U63") (pin "15") (pinfunction "VS-_15") (pintype "power_in"))
      (node (ref "U63") (pin "17") (pinfunction "EPAD_17") (pintype "passive"))
      (node (ref "U67") (pin "14") (pinfunction "LVSS_14") (pintype "power_in"))
      (node (ref "U67") (pin "15") (pinfunction "VS-_15") (pintype "power_in"))
      (node (ref "U67") (pin "17") (pinfunction "EPAD_17") (pintype "passive"))
    )
    (net (code "71") (name "unconnected-(U62-NC-Pad8)") (class "Default")
      (node (ref "U62") (pin "8") (pinfunction "NC_8") (pintype "passive"))
    )
    (net (code "72") (name "unconnected-(U63-NC-Pad8)") (class "Default")
      (node (ref "U63") (pin "8") (pinfunction "NC_8") (pintype "passive"))
    )
    (net (code "73") (name "unconnected-(U66-NC-Pad1)") (class "Default")
      (node (ref "U66") (pin "1") (pinfunction "NC_1") (pintype "passive"))
    )
    (net (code "74") (name "unconnected-(U67-NC-Pad8)") (class "Default")
      (node (ref "U67") (pin "8") (pinfunction "NC_8") (pintype "passive"))
    )
  )
)
